# CM5_GPIO.net
KiCad netlist of a schematic drawn in Altium Designer
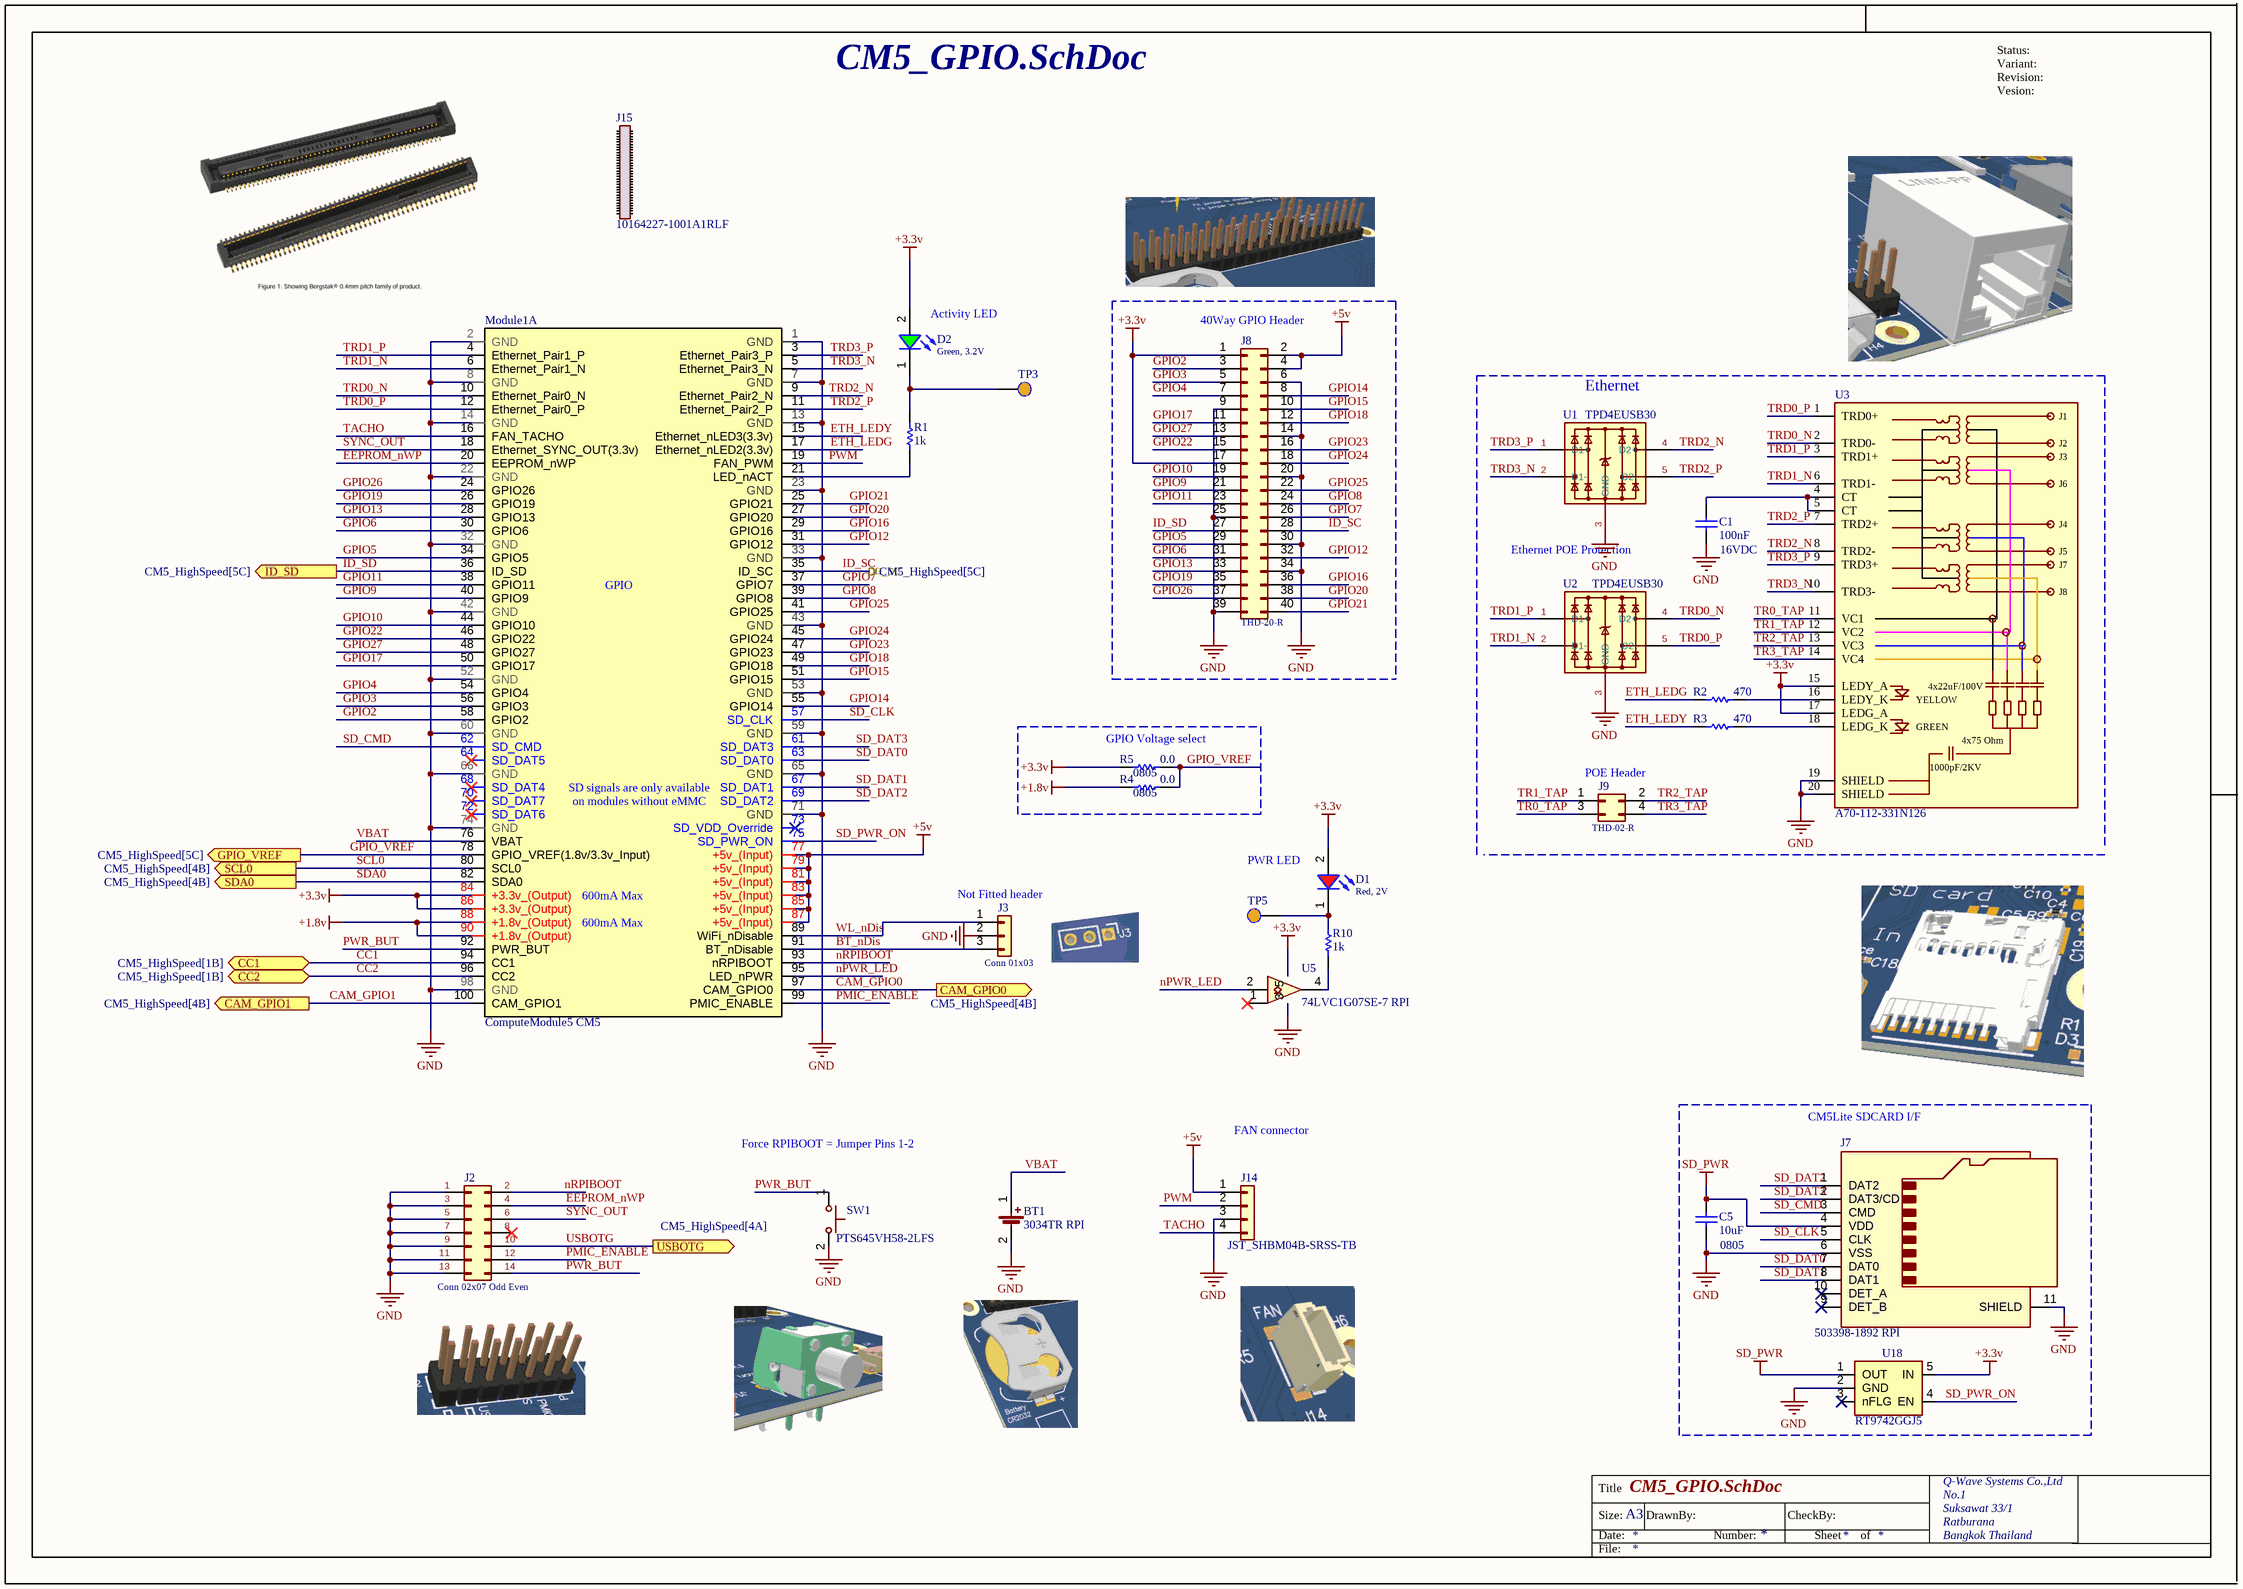
[diagram p0: CM5_GPIO.SchDoc]

(export (version "E")
  (design (tool "Eeschema 10.0.6"))
  (components
    (comp (ref "BT1")
      (value "3034TR RPI")
      (footprint "3034TR RPI")
      (description "Coin Cell Battery Holders COIN CELL RETAINER T APE/REEL 500PC")
      (libsource (lib "Q-WAVE SYSTEMS CO") (part "3034TR RPI"))
    )
    (comp (ref "C1")
      (value "100nF")
      (footprint "WCAP-CSGP_0402_H=0.5mm")
      (description "WCAP-CSGP Multilayer Ceramic Chip Capacitor, General Purpose, size 0402, X5R, 100nF, 16V")
      (fields
        (field (name "MANUFACTURER PART NUMBER") "885012105016")
        (field (name "MANUFACTURER") "Wurth Elektronik")
        (field (name "RATED VOLTAGE") "16VDC")
      )
      (libsource (lib "") (part "Symbol_2"))
    )
    (comp (ref "C5")
      (value "10uF")
      (footprint "WCAP-CSGP_0805_H=1.25mm")
      (description "WCAP-CSGP Multilayer Ceramic Chip Capacitor, General Purpose, size 0805, X5R, 10uF, 16V")
      (fields
        (field (name "MANUFACTURER") "Wurth Elektronik")
        (field (name "MANUFACTURER PART NUMBER") "885012107014")
        (field (name "SIZE") "0805")
      )
      (libsource (lib "") (part "Symbol_2"))
    )
    (comp (ref "D1")
      (value "Red, 2V")
      (footprint "WL-SMCW_0603_H=0.7mm_Red")
      (description "WL-SMCW SMT Mono-color Chip LED Waterclear, size 0603, Red, 2V, 140deg")
      (fields (field (name "PART NUMBER") "150060RS75000") (field (name "PUBLISHER") "Wurth Elektronik"))
      (libsource (lib "Q-WAVE SYSTEMS CO") (part "Symbol"))
    )
    (comp (ref "D2")
      (value "Green, 3.2V")
      (footprint "WL-SMCW_0603_H=0.7mm_Green")
      (description "WL-SMCW SMT Mono-color Chip LED Waterclear, size 0603, Green, 3.2V, 140deg")
      (fields (field (name "PART NUMBER") "150060GS75000") (field (name "PUBLISHER") "Wurth Elektronik"))
      (libsource (lib "Q-WAVE SYSTEMS CO") (part "Symbol"))
    )
    (comp (ref "J2")
      (value "Conn 02x07 Odd Even")
      (footprint "Conn 02x07 Odd Even")
      (description "PinHeader 2x07 P2.54mm Vertical")
      (fields
        (field (name "MANUFACTURER") "Wurth Elektronik")
        (field (name "MANUFACTURER PART NUMBER") "61301421121")
      )
      (libsource (lib "Q-WAVE SYSTEMS CO") (part "Conn 02x07 Odd Even"))
    )
    (comp (ref "J3")
      (value "Conn 01x03")
      (footprint "Conn 01x03")
      (description "PinHeader_1x03_P2.54mm_Vertical")
      (fields
        (field (name "MANUFACTURER") "Wurth Elektronik")
        (field (name "MANUFACTURER PART NUMBER") "61300311121")
      )
      (libsource (lib "Q-WAVE SYSTEMS CO") (part "Conn 01x03"))
    )
    (comp (ref "J7")
      (value "503398-1892 RPI")
      (footprint "503398-1892 RPI")
      (libsource (lib "Q-WAVE SYSTEMS CO") (part "503398-1892 RPI"))
    )
    (comp (ref "J8")
      (value "THD-20-R")
      (footprint "THD-20-R")
      (description "Through hole straight pin header, 2x20, 2.54mm pitch, double rows")
      (fields
        (field (name "MANUFACTURER PART NUMBER") "61304021121")
        (field (name "MANUFACTURER") "Wurth Elektronik")
      )
      (libsource (lib "Q-WAVE SYSTEMS CO") (part "THD-20-R"))
    )
    (comp (ref "J9")
      (value "THD-02-R")
      (footprint "THD-02-R")
      (description "PinHeader 2x02 P2.54mm Vertical")
      (fields
        (field (name "MANUFACTURER") "Wurth Elektronik")
        (field (name "MANUFACTURER PART NUMBER") "61300421121")
      )
      (libsource (lib "Q-WAVE SYSTEMS CO") (part "THD-02-R"))
    )
    (comp (ref "J14")
      (value "JST_SHBM04B-SRSS-TB")
      (footprint "JST_SHBM04B-SRSS-TB")
      (description "Board Connector, 4 Contact(s), 1 Row(s), Male, Straight, Surface Mount Terminal")
      (libsource (lib "Q-WAVE SYSTEMS CO") (part "JST_SHBM04B-SRSS-TB"))
    )
    (comp (ref "J15")
      (value "10164227-1001A1RLF")
      (footprint "CM5-BergStak-10164227")
      (description "CM5 1.5mm Height 0.4MM Btb, 100P, Receptacle, 1.5MM Stack Height")
      (libsource (lib "Q-WAVE SYSTEMS CO") (part "10164227-1001A1RLF"))
    )
    (comp (ref "Module1")
      (value "ComputeModule5 CM5")
      (footprint "ComputeModule5-CM5")
      (description "Raspberry Pi Compute Module 5")
      (libsource (lib "Q-WAVE SYSTEMS CO") (part "ComputeModule5-CM5"))
    )
    (comp (ref "R1")
      (value "1k")
      (footprint "SMD-0402-RES")
      (description "RES SMD 1K OHM 1% 1/10W 0402")
      (fields
        (field (name "MANUFACTURER") "Panasonic Electronic Components")
        (field (name "TOLERANCE") "±1%")
      )
      (libsource (lib "Q-WAVE SYSTEMS CO") (part "resistor"))
    )
    (comp (ref "R2")
      (value "470")
      (footprint "SMD-0402-RES")
      (description "RES SMD 470 OHM 1% 1/10W 0402")
      (fields (field (name "PART NUMBER") "ERJ-2RKF4700X") (field (name "DIGI-KEY PART NUMBER") "P470LCT-ND"))
      (libsource (lib "Q-WAVE SYSTEMS CO") (part "resistor"))
    )
    (comp (ref "R3")
      (value "470")
      (footprint "SMD-0402-RES")
      (description "RES SMD 470 OHM 1% 1/10W 0402")
      (fields (field (name "PART NUMBER") "ERJ-2RKF4700X") (field (name "DIGI-KEY PART NUMBER") "P470LCT-ND"))
      (libsource (lib "Q-WAVE SYSTEMS CO") (part "resistor"))
    )
    (comp (ref "R4")
      (value "0.0")
      (footprint "SMD-0805-RES")
      (description "RES SMD 0.0 OHM JUMPER 1/8W 0805")
      (fields
        (field (name "TOLERANCE") "Jumper")
        (field (name "PART NUMBER") "ERJ-6GEY0R00V")
        (field (name "SUPPLIER DEVICE PACKAGE") "0805")
      )
      (libsource (lib "") (part "Symbol_1"))
    )
    (comp (ref "R5")
      (value "0.0")
      (footprint "SMD-0805-RES")
      (description "RES SMD 0.0 OHM JUMPER 1/8W 0805")
      (fields
        (field (name "TOLERANCE") "Jumper")
        (field (name "PART NUMBER") "ERJ-6GEY0R00V")
        (field (name "SUPPLIER DEVICE PACKAGE") "0805")
      )
      (libsource (lib "") (part "Symbol_1"))
    )
    (comp (ref "R10")
      (value "1k")
      (footprint "SMD-0402-RES")
      (description "RES SMD 1K OHM 1% 1/10W 0402")
      (fields
        (field (name "MANUFACTURER") "Panasonic Electronic Components")
        (field (name "TOLERANCE") "±1%")
      )
      (libsource (lib "Q-WAVE SYSTEMS CO") (part "resistor"))
    )
    (comp (ref "SW1")
      (value "PTS645VH58-2LFS")
      (footprint "PTS645VH58-2LFS")
      (description "PTS645 Series Compact 6 x 6 mm SPST 2 N Through Hole Tactile Switch")
      (libsource (lib "Q-WAVE SYSTEMS CO") (part "PTS645VH58-2LFS"))
    )
    (comp (ref "TP3")
      (value "TEST_POINT 1")
      (footprint "TEST_POINT 1")
      (description "Test Point SMT PAD")
      (libsource (lib "Q-WAVE SYSTEMS CO") (part "TEST_POINT 1"))
    )
    (comp (ref "TP5")
      (value "TEST_POINT 1")
      (footprint "TEST_POINT 1")
      (description "Test Point SMT PAD")
      (libsource (lib "Q-WAVE SYSTEMS CO") (part "TEST_POINT 1"))
    )
    (comp (ref "U1")
      (value "TPD4EUSB30")
      (footprint "TPD4EUSB30")
      (libsource (lib "Q-WAVE SYSTEMS CO") (part "TPD4EUSB30"))
    )
    (comp (ref "U2")
      (value "TPD4EUSB30")
      (footprint "TPD4EUSB30")
      (libsource (lib "Q-WAVE SYSTEMS CO") (part "TPD4EUSB30"))
    )
    (comp (ref "U3")
      (value "A70-112-331N126")
      (footprint "A70-112-331N126")
      (libsource (lib "Q-WAVE SYSTEMS CO") (part "A70-112-331N126"))
    )
    (comp (ref "U5")
      (value "74LVC1G07SE-7 RPI")
      (footprint "74LVC1G07SE-7 RPI")
      (description "74LVC Series 5.5 V Surface Mount Single Buffer with Open Drain Output - SOT-353")
      (libsource (lib "Q-WAVE SYSTEMS CO") (part "74LVC1G07SE-7 RPI"))
    )
    (comp (ref "U18")
      (value "RT9742GGJ5")
      (footprint "FP-RT9742GGJ5-IPC_A")
      (description "IC Pwr Swtch N-chan 1: 1 TSOT23-5")
      (libsource (lib "Q-WAVE SYSTEMS CO") (part "RT9742GGJ5"))
    )
  )
  (nets
    (net (code "1") (name "+1.8v") (class "Default")
      (node (ref "Module1") (pin "88") (pinfunction "+1.8v_(Output)_88") (pintype "passive"))
      (node (ref "Module1") (pin "90") (pinfunction "+1.8v_(Output)_90") (pintype "passive"))
      (node (ref "R4") (pin "1") (pinfunction "1_1") (pintype "passive"))
    )
    (net (code "2") (name "+3.3v") (class "Default")
      (node (ref "D1") (pin "2") (pinfunction "A_2") (pintype "passive"))
      (node (ref "D2") (pin "2") (pinfunction "A_2") (pintype "passive"))
      (node (ref "J8") (pin "1") (pinfunction "Pin_1_1") (pintype "passive"))
      (node (ref "J8") (pin "17") (pinfunction "Pin_17_17") (pintype "passive"))
      (node (ref "Module1") (pin "84") (pinfunction "+3.3v_(Output)_84") (pintype "passive"))
      (node (ref "Module1") (pin "86") (pinfunction "+3.3v_(Output)_86") (pintype "passive"))
      (node (ref "R5") (pin "1") (pinfunction "1_1") (pintype "passive"))
      (node (ref "U18") (pin "5") (pinfunction "IN_5") (pintype "passive"))
      (node (ref "U3") (pin "15") (pinfunction "LEDY_A_15") (pintype "passive"))
      (node (ref "U3") (pin "17") (pinfunction "LEDG_A_17") (pintype "passive"))
      (node (ref "U5") (pin "5") (pinfunction "VCC_5") (pintype "passive"))
    )
    (net (code "3") (name "+5v") (class "Default")
      (node (ref "J14") (pin "1") (pinfunction "Pin_1_1") (pintype "passive"))
      (node (ref "J8") (pin "2") (pinfunction "Pin_2_2") (pintype "passive"))
      (node (ref "J8") (pin "4") (pinfunction "Pin_4_4") (pintype "passive"))
      (node (ref "Module1") (pin "77") (pinfunction "+5v_(Input)_77") (pintype "passive"))
      (node (ref "Module1") (pin "79") (pinfunction "+5v_(Input)_79") (pintype "passive"))
      (node (ref "Module1") (pin "81") (pinfunction "+5v_(Input)_81") (pintype "passive"))
      (node (ref "Module1") (pin "83") (pinfunction "+5v_(Input)_83") (pintype "passive"))
      (node (ref "Module1") (pin "85") (pinfunction "+5v_(Input)_85") (pintype "passive"))
      (node (ref "Module1") (pin "87") (pinfunction "+5v_(Input)_87") (pintype "passive"))
    )
    (net (code "4") (name "/BT_nDis") (class "Default")
      (node (ref "J3") (pin "3") (pinfunction "Pin_3_3") (pintype "passive"))
      (node (ref "Module1") (pin "91") (pinfunction "BT_nDisable_91") (pintype "passive"))
    )
    (net (code "5") (name "/CAM_GPIO0") (class "Default")
      (node (ref "Module1") (pin "97") (pinfunction "CAM_GPIO0_97") (pintype "passive"))
    )
    (net (code "6") (name "/CAM_GPIO1") (class "Default")
      (node (ref "Module1") (pin "100") (pinfunction "CAM_GPIO1_100") (pintype "passive"))
    )
    (net (code "7") (name "/CC1") (class "Default")
      (node (ref "Module1") (pin "94") (pinfunction "CC1_94") (pintype "passive"))
    )
    (net (code "8") (name "/CC2") (class "Default")
      (node (ref "Module1") (pin "96") (pinfunction "CC2_96") (pintype "passive"))
    )
    (net (code "9") (name "/EEPROM_nWP") (class "Default")
      (node (ref "J2") (pin "4") (pinfunction "Pin_4_4") (pintype "passive"))
      (node (ref "Module1") (pin "20") (pinfunction "EEPROM_nWP_20") (pintype "passive"))
    )
    (net (code "10") (name "/ETH_LEDG") (class "Default")
      (node (ref "Module1") (pin "17") (pinfunction "Ethernet_nLED2(3.3v)_17") (pintype "passive"))
      (node (ref "R2") (pin "1") (pinfunction "1_1") (pintype "passive"))
    )
    (net (code "11") (name "/ETH_LEDY") (class "Default")
      (node (ref "Module1") (pin "15") (pinfunction "Ethernet_nLED3(3.3v)_15") (pintype "passive"))
      (node (ref "R3") (pin "1") (pinfunction "1_1") (pintype "passive"))
    )
    (net (code "12") (name "/GPIO2") (class "Default")
      (node (ref "J8") (pin "3") (pinfunction "Pin_3_3") (pintype "passive"))
      (node (ref "Module1") (pin "58") (pinfunction "GPIO2_58") (pintype "passive"))
    )
    (net (code "13") (name "/GPIO3") (class "Default")
      (node (ref "J8") (pin "5") (pinfunction "Pin_5_5") (pintype "passive"))
      (node (ref "Module1") (pin "56") (pinfunction "GPIO3_56") (pintype "passive"))
    )
    (net (code "14") (name "/GPIO4") (class "Default")
      (node (ref "J8") (pin "7") (pinfunction "Pin_7_7") (pintype "passive"))
      (node (ref "Module1") (pin "54") (pinfunction "GPIO4_54") (pintype "passive"))
    )
    (net (code "15") (name "/GPIO5") (class "Default")
      (node (ref "J8") (pin "29") (pinfunction "Pin_29_29") (pintype "passive"))
      (node (ref "Module1") (pin "34") (pinfunction "GPIO5_34") (pintype "passive"))
    )
    (net (code "16") (name "/GPIO6") (class "Default")
      (node (ref "J8") (pin "31") (pinfunction "Pin_31_31") (pintype "passive"))
      (node (ref "Module1") (pin "30") (pinfunction "GPIO6_30") (pintype "passive"))
    )
    (net (code "17") (name "/GPIO7") (class "Default")
      (node (ref "J8") (pin "26") (pinfunction "Pin_26_26") (pintype "passive"))
      (node (ref "Module1") (pin "37") (pinfunction "GPIO7_37") (pintype "passive"))
    )
    (net (code "18") (name "/GPIO8") (class "Default")
      (node (ref "J8") (pin "24") (pinfunction "Pin_24_24") (pintype "passive"))
      (node (ref "Module1") (pin "39") (pinfunction "GPIO8_39") (pintype "passive"))
    )
    (net (code "19") (name "/GPIO9") (class "Default")
      (node (ref "J8") (pin "21") (pinfunction "Pin_21_21") (pintype "passive"))
      (node (ref "Module1") (pin "40") (pinfunction "GPIO9_40") (pintype "passive"))
    )
    (net (code "20") (name "/GPIO10") (class "Default")
      (node (ref "J8") (pin "19") (pinfunction "Pin_19_19") (pintype "passive"))
      (node (ref "Module1") (pin "44") (pinfunction "GPIO10_44") (pintype "passive"))
    )
    (net (code "21") (name "/GPIO11") (class "Default")
      (node (ref "J8") (pin "23") (pinfunction "Pin_23_23") (pintype "passive"))
      (node (ref "Module1") (pin "38") (pinfunction "GPIO11_38") (pintype "passive"))
    )
    (net (code "22") (name "/GPIO12") (class "Default")
      (node (ref "J8") (pin "32") (pinfunction "Pin_32_32") (pintype "passive"))
      (node (ref "Module1") (pin "31") (pinfunction "GPIO12_31") (pintype "passive"))
    )
    (net (code "23") (name "/GPIO13") (class "Default")
      (node (ref "J8") (pin "33") (pinfunction "Pin_33_33") (pintype "passive"))
      (node (ref "Module1") (pin "28") (pinfunction "GPIO13_28") (pintype "passive"))
    )
    (net (code "24") (name "/GPIO14") (class "Default")
      (node (ref "J8") (pin "8") (pinfunction "Pin_8_8") (pintype "passive"))
      (node (ref "Module1") (pin "55") (pinfunction "GPIO14_55") (pintype "passive"))
    )
    (net (code "25") (name "/GPIO15") (class "Default")
      (node (ref "J8") (pin "10") (pinfunction "Pin_10_10") (pintype "passive"))
      (node (ref "Module1") (pin "51") (pinfunction "GPIO15_51") (pintype "passive"))
    )
    (net (code "26") (name "/GPIO16") (class "Default")
      (node (ref "J8") (pin "36") (pinfunction "Pin_36_36") (pintype "passive"))
      (node (ref "Module1") (pin "29") (pinfunction "GPIO16_29") (pintype "passive"))
    )
    (net (code "27") (name "/GPIO17") (class "Default")
      (node (ref "J8") (pin "11") (pinfunction "Pin_11_11") (pintype "passive"))
      (node (ref "Module1") (pin "50") (pinfunction "GPIO17_50") (pintype "passive"))
    )
    (net (code "28") (name "/GPIO18") (class "Default")
      (node (ref "J8") (pin "12") (pinfunction "Pin_12_12") (pintype "passive"))
      (node (ref "Module1") (pin "49") (pinfunction "GPIO18_49") (pintype "passive"))
    )
    (net (code "29") (name "/GPIO19") (class "Default")
      (node (ref "J8") (pin "35") (pinfunction "Pin_35_35") (pintype "passive"))
      (node (ref "Module1") (pin "26") (pinfunction "GPIO19_26") (pintype "passive"))
    )
    (net (code "30") (name "/GPIO20") (class "Default")
      (node (ref "J8") (pin "38") (pinfunction "Pin_38_38") (pintype "passive"))
      (node (ref "Module1") (pin "27") (pinfunction "GPIO20_27") (pintype "passive"))
    )
    (net (code "31") (name "/GPIO21") (class "Default")
      (node (ref "J8") (pin "40") (pinfunction "Pin_40_40") (pintype "passive"))
      (node (ref "Module1") (pin "25") (pinfunction "GPIO21_25") (pintype "passive"))
    )
    (net (code "32") (name "/GPIO22") (class "Default")
      (node (ref "J8") (pin "15") (pinfunction "Pin_15_15") (pintype "passive"))
      (node (ref "Module1") (pin "46") (pinfunction "GPIO22_46") (pintype "passive"))
    )
    (net (code "33") (name "/GPIO23") (class "Default")
      (node (ref "J8") (pin "16") (pinfunction "Pin_16_16") (pintype "passive"))
      (node (ref "Module1") (pin "47") (pinfunction "GPIO23_47") (pintype "passive"))
    )
    (net (code "34") (name "/GPIO24") (class "Default")
      (node (ref "J8") (pin "18") (pinfunction "Pin_18_18") (pintype "passive"))
      (node (ref "Module1") (pin "45") (pinfunction "GPIO24_45") (pintype "passive"))
    )
    (net (code "35") (name "/GPIO25") (class "Default")
      (node (ref "J8") (pin "22") (pinfunction "Pin_22_22") (pintype "passive"))
      (node (ref "Module1") (pin "41") (pinfunction "GPIO25_41") (pintype "passive"))
    )
    (net (code "36") (name "/GPIO26") (class "Default")
      (node (ref "J8") (pin "37") (pinfunction "Pin_37_37") (pintype "passive"))
      (node (ref "Module1") (pin "24") (pinfunction "GPIO26_24") (pintype "passive"))
    )
    (net (code "37") (name "/GPIO27") (class "Default")
      (node (ref "J8") (pin "13") (pinfunction "Pin_13_13") (pintype "passive"))
      (node (ref "Module1") (pin "48") (pinfunction "GPIO27_48") (pintype "passive"))
    )
    (net (code "38") (name "/GPIO_VREF") (class "Default")
      (node (ref "Module1") (pin "78") (pinfunction "GPIO_VREF(1.8v/3.3v_Input)_78") (pintype "passive"))
      (node (ref "R4") (pin "2") (pinfunction "2_2") (pintype "passive"))
      (node (ref "R5") (pin "2") (pinfunction "2_2") (pintype "passive"))
    )
    (net (code "39") (name "/ID_SC") (class "Default")
      (node (ref "J8") (pin "28") (pinfunction "Pin_28_28") (pintype "passive"))
      (node (ref "Module1") (pin "35") (pinfunction "ID_SC_35") (pintype "passive"))
    )
    (net (code "40") (name "/ID_SD") (class "Default")
      (node (ref "J8") (pin "27") (pinfunction "Pin_27_27") (pintype "passive"))
      (node (ref "Module1") (pin "36") (pinfunction "ID_SD_36") (pintype "passive"))
    )
    (net (code "41") (name "/PMIC_ENABLE") (class "Default")
      (node (ref "J2") (pin "12") (pinfunction "Pin_12_12") (pintype "passive"))
      (node (ref "Module1") (pin "99") (pinfunction "PMIC_ENABLE_99") (pintype "passive"))
    )
    (net (code "42") (name "/PWM") (class "Default")
      (node (ref "J14") (pin "2") (pinfunction "Pin_2_2") (pintype "passive"))
      (node (ref "Module1") (pin "19") (pinfunction "FAN_PWM_19") (pintype "passive"))
    )
    (net (code "43") (name "/PWR_BUT") (class "Default")
      (node (ref "J2") (pin "14") (pinfunction "Pin_14_14") (pintype "passive"))
      (node (ref "Module1") (pin "92") (pinfunction "PWR_BUT_92") (pintype "passive"))
      (node (ref "SW1") (pin "1") (pinfunction "1_1") (pintype "passive"))
    )
    (net (code "44") (name "/SCL0") (class "Default")
      (node (ref "Module1") (pin "80") (pinfunction "SCL0_80") (pintype "passive"))
    )
    (net (code "45") (name "/SDA0") (class "Default")
      (node (ref "Module1") (pin "82") (pinfunction "SDA0_82") (pintype "passive"))
    )
    (net (code "46") (name "/SD_CLK") (class "Default")
      (node (ref "J7") (pin "5") (pinfunction "CLK_5") (pintype "passive"))
      (node (ref "Module1") (pin "57") (pinfunction "SD_CLK_57") (pintype "passive"))
    )
    (net (code "47") (name "/SD_CMD") (class "Default")
      (node (ref "J7") (pin "3") (pinfunction "CMD_3") (pintype "passive"))
      (node (ref "Module1") (pin "62") (pinfunction "SD_CMD_62") (pintype "passive"))
    )
    (net (code "48") (name "/SD_DAT0") (class "Default")
      (node (ref "J7") (pin "7") (pinfunction "DAT0_7") (pintype "passive"))
      (node (ref "Module1") (pin "63") (pinfunction "SD_DAT0_63") (pintype "passive"))
    )
    (net (code "49") (name "/SD_DAT1") (class "Default")
      (node (ref "J7") (pin "8") (pinfunction "DAT1_8") (pintype "passive"))
      (node (ref "Module1") (pin "67") (pinfunction "SD_DAT1_67") (pintype "passive"))
    )
    (net (code "50") (name "/SD_DAT2") (class "Default")
      (node (ref "J7") (pin "1") (pinfunction "DAT2_1") (pintype "passive"))
      (node (ref "Module1") (pin "69") (pinfunction "SD_DAT2_69") (pintype "passive"))
    )
    (net (code "51") (name "/SD_DAT3") (class "Default")
      (node (ref "J7") (pin "2") (pinfunction "DAT3/CD_2") (pintype "passive"))
      (node (ref "Module1") (pin "61") (pinfunction "SD_DAT3_61") (pintype "passive"))
    )
    (net (code "52") (name "/SD_PWR_ON") (class "Default")
      (node (ref "Module1") (pin "75") (pinfunction "SD_PWR_ON_75") (pintype "passive"))
      (node (ref "U18") (pin "4") (pinfunction "EN_4") (pintype "passive"))
    )
    (net (code "53") (name "/SYNC_OUT") (class "Default")
      (node (ref "J2") (pin "6") (pinfunction "Pin_6_6") (pintype "passive"))
      (node (ref "Module1") (pin "18") (pinfunction "Ethernet_SYNC_OUT(3.3v)_18") (pintype "passive"))
    )
    (net (code "54") (name "/TACHO") (class "Default")
      (node (ref "J14") (pin "4") (pinfunction "Pin_4_4") (pintype "passive"))
      (node (ref "Module1") (pin "16") (pinfunction "FAN_TACHO_16") (pintype "passive"))
    )
    (net (code "55") (name "/TR0_TAP") (class "Default")
      (node (ref "J9") (pin "3") (pinfunction "Pin_3_3") (pintype "passive"))
      (node (ref "U3") (pin "11") (pinfunction "VC1_11") (pintype "passive"))
    )
    (net (code "56") (name "/TR1_TAP") (class "Default")
      (node (ref "J9") (pin "1") (pinfunction "Pin_1_1") (pintype "passive"))
      (node (ref "U3") (pin "12") (pinfunction "VC2_12") (pintype "passive"))
    )
    (net (code "57") (name "/TR2_TAP") (class "Default")
      (node (ref "J9") (pin "2") (pinfunction "Pin_2_2") (pintype "passive"))
      (node (ref "U3") (pin "13") (pinfunction "VC3_13") (pintype "passive"))
    )
    (net (code "58") (name "/TR3_TAP") (class "Default")
      (node (ref "J9") (pin "4") (pinfunction "Pin_4_4") (pintype "passive"))
      (node (ref "U3") (pin "14") (pinfunction "VC4_14") (pintype "passive"))
    )
    (net (code "59") (name "/TRD0_N") (class "Default")
      (node (ref "Module1") (pin "10") (pinfunction "Ethernet_Pair0_N_10") (pintype "passive"))
      (node (ref "U2") (pin "4") (pinfunction "D2+_4") (pintype "passive"))
      (node (ref "U3") (pin "2") (pinfunction "TRD0-_2") (pintype "passive"))
    )
    (net (code "60") (name "/TRD0_P") (class "Default")
      (node (ref "Module1") (pin "12") (pinfunction "Ethernet_Pair0_P_12") (pintype "passive"))
      (node (ref "U2") (pin "5") (pinfunction "D2-_5") (pintype "passive"))
      (node (ref "U3") (pin "1") (pinfunction "TRD0+_1") (pintype "passive"))
    )
    (net (code "61") (name "/TRD1_N") (class "Default")
      (node (ref "Module1") (pin "6") (pinfunction "Ethernet_Pair1_N_6") (pintype "passive"))
      (node (ref "U2") (pin "2") (pinfunction "D1-_2") (pintype "passive"))
      (node (ref "U3") (pin "6") (pinfunction "TRD1-_6") (pintype "passive"))
    )
    (net (code "62") (name "/TRD1_P") (class "Default")
      (node (ref "Module1") (pin "4") (pinfunction "Ethernet_Pair1_P_4") (pintype "passive"))
      (node (ref "U2") (pin "1") (pinfunction "D1+_1") (pintype "passive"))
      (node (ref "U3") (pin "3") (pinfunction "TRD1+_3") (pintype "passive"))
    )
    (net (code "63") (name "/TRD2_N") (class "Default")
      (node (ref "Module1") (pin "9") (pinfunction "Ethernet_Pair2_N_9") (pintype "passive"))
      (node (ref "U1") (pin "4") (pinfunction "D2+_4") (pintype "passive"))
      (node (ref "U3") (pin "8") (pinfunction "TRD2-_8") (pintype "passive"))
    )
    (net (code "64") (name "/TRD2_P") (class "Default")
      (node (ref "Module1") (pin "11") (pinfunction "Ethernet_Pair2_P_11") (pintype "passive"))
      (node (ref "U1") (pin "5") (pinfunction "D2-_5") (pintype "passive"))
      (node (ref "U3") (pin "7") (pinfunction "TRD2+_7") (pintype "passive"))
    )
    (net (code "65") (name "/TRD3_N") (class "Default")
      (node (ref "Module1") (pin "5") (pinfunction "Ethernet_Pair3_N_5") (pintype "passive"))
      (node (ref "U1") (pin "2") (pinfunction "D1-_2") (pintype "passive"))
      (node (ref "U3") (pin "10") (pinfunction "TRD3-_10") (pintype "passive"))
    )
    (net (code "66") (name "/TRD3_P") (class "Default")
      (node (ref "Module1") (pin "3") (pinfunction "Ethernet_Pair3_P_3") (pintype "passive"))
      (node (ref "U1") (pin "1") (pinfunction "D1+_1") (pintype "passive"))
      (node (ref "U3") (pin "9") (pinfunction "TRD3+_9") (pintype "passive"))
    )
    (net (code "67") (name "/USBOTG") (class "Default")
      (node (ref "J2") (pin "10") (pinfunction "Pin_10_10") (pintype "passive"))
    )
    (net (code "68") (name "/VBAT") (class "Default")
      (node (ref "BT1") (pin "1") (pinfunction "+_1") (pintype "passive"))
      (node (ref "Module1") (pin "76") (pinfunction "VBAT_76") (pintype "passive"))
    )
    (net (code "69") (name "/WL_nDis") (class "Default")
      (node (ref "J3") (pin "1") (pinfunction "Pin_1_1") (pintype "passive"))
      (node (ref "Module1") (pin "89") (pinfunction "WiFi_nDisable_89") (pintype "passive"))
    )
    (net (code "70") (name "/nPWR_LED") (class "Default")
      (node (ref "Module1") (pin "95") (pinfunction "LED_nPWR_95") (pintype "passive"))
      (node (ref "U5") (pin "2") (pinfunction "2_2") (pintype "passive"))
    )
    (net (code "71") (name "/nRPIBOOT") (class "Default")
      (node (ref "J2") (pin "2") (pinfunction "Pin_2_2") (pintype "passive"))
      (node (ref "Module1") (pin "93") (pinfunction "nRPIBOOT_93") (pintype "passive"))
    )
    (net (code "72") (name "GND") (class "Default")
      (node (ref "BT1") (pin "2") (pinfunction "-_2") (pintype "passive"))
      (node (ref "C1") (pin "1") (pinfunction "1_1") (pintype "passive"))
      (node (ref "C5") (pin "1") (pinfunction "1_1") (pintype "passive"))
      (node (ref "J14") (pin "3") (pinfunction "Pin_3_3") (pintype "passive"))
      (node (ref "J2") (pin "1") (pinfunction "Pin_1_1") (pintype "passive"))
      (node (ref "J2") (pin "11") (pinfunction "Pin_11_11") (pintype "passive"))
      (node (ref "J2") (pin "13") (pinfunction "Pin_13_13") (pintype "passive"))
      (node (ref "J2") (pin "3") (pinfunction "Pin_3_3") (pintype "passive"))
      (node (ref "J2") (pin "5") (pinfunction "Pin_5_5") (pintype "passive"))
      (node (ref "J2") (pin "7") (pinfunction "Pin_7_7") (pintype "passive"))
      (node (ref "J2") (pin "9") (pinfunction "Pin_9_9") (pintype "passive"))
      (node (ref "J3") (pin "2") (pinfunction "Pin_2_2") (pintype "passive"))
      (node (ref "J7") (pin "11") (pinfunction "SHIELD_11") (pintype "passive"))
      (node (ref "J7") (pin "6") (pinfunction "VSS_6") (pintype "passive"))
      (node (ref "J8") (pin "14") (pinfunction "Pin_14_14") (pintype "passive"))
      (node (ref "J8") (pin "20") (pinfunction "Pin_20_20") (pintype "passive"))
      (node (ref "J8") (pin "25") (pinfunction "Pin_25_25") (pintype "passive"))
      (node (ref "J8") (pin "30") (pinfunction "Pin_30_30") (pintype "passive"))
      (node (ref "J8") (pin "34") (pinfunction "Pin_34_34") (pintype "passive"))
      (node (ref "J8") (pin "39") (pinfunction "Pin_39_39") (pintype "passive"))
      (node (ref "J8") (pin "6") (pinfunction "Pin_6_6") (pintype "passive"))
      (node (ref "J8") (pin "9") (pinfunction "Pin_9_9") (pintype "passive"))
      (node (ref "Module1") (pin "1") (pinfunction "GND_1") (pintype "passive"))
      (node (ref "Module1") (pin "13") (pinfunction "GND_13") (pintype "passive"))
      (node (ref "Module1") (pin "14") (pinfunction "GND_14") (pintype "passive"))
      (node (ref "Module1") (pin "2") (pinfunction "GND_2") (pintype "passive"))
      (node (ref "Module1") (pin "22") (pinfunction "GND_22") (pintype "passive"))
      (node (ref "Module1") (pin "23") (pinfunction "GND_23") (pintype "passive"))
      (node (ref "Module1") (pin "32") (pinfunction "GND_32") (pintype "passive"))
      (node (ref "Module1") (pin "33") (pinfunction "GND_33") (pintype "passive"))
      (node (ref "Module1") (pin "42") (pinfunction "GND_42") (pintype "passive"))
      (node (ref "Module1") (pin "43") (pinfunction "GND_43") (pintype "passive"))
      (node (ref "Module1") (pin "52") (pinfunction "GND_52") (pintype "passive"))
      (node (ref "Module1") (pin "53") (pinfunction "GND_53") (pintype "passive"))
      (node (ref "Module1") (pin "59") (pinfunction "GND_59") (pintype "passive"))
      (node (ref "Module1") (pin "60") (pinfunction "GND_60") (pintype "passive"))
      (node (ref "Module1") (pin "65") (pinfunction "GND_65") (pintype "passive"))
      (node (ref "Module1") (pin "66") (pinfunction "GND_66") (pintype "passive"))
      (node (ref "Module1") (pin "7") (pinfunction "GND_7") (pintype "passive"))
      (node (ref "Module1") (pin "71") (pinfunction "GND_71") (pintype "passive"))
      (node (ref "Module1") (pin "74") (pinfunction "GND_74") (pintype "passive"))
      (node (ref "Module1") (pin "8") (pinfunction "GND_8") (pintype "passive"))
      (node (ref "Module1") (pin "98") (pinfunction "GND_98") (pintype "passive"))
      (node (ref "SW1") (pin "2") (pinfunction "2_2") (pintype "passive"))
      (node (ref "U1") (pin "3") (pinfunction "GND_3") (pintype "passive"))
      (node (ref "U18") (pin "2") (pinfunction "GND_2") (pintype "passive"))
      (node (ref "U2") (pin "3") (pinfunction "GND_3") (pintype "passive"))
      (node (ref "U3") (pin "19") (pinfunction "SHIELD_19") (pintype "passive"))
      (node (ref "U3") (pin "20") (pinfunction "SHIELD_20") (pintype "passive"))
      (node (ref "U5") (pin "3") (pinfunction "GND_3") (pintype "passive"))
    )
    (net (code "73") (name "Net-(C1-Pad2)") (class "Default")
      (node (ref "C1") (pin "2") (pinfunction "2_2") (pintype "passive"))
      (node (ref "U3") (pin "4") (pinfunction "CT_4") (pintype "passive"))
      (node (ref "U3") (pin "5") (pinfunction "CT_5") (pintype "passive"))
    )
    (net (code "74") (name "Net-(D1-K)") (class "Default")
      (node (ref "D1") (pin "1") (pinfunction "K_1") (pintype "passive"))
      (node (ref "R10") (pin "2") (pinfunction "2_2") (pintype "passive"))
      (node (ref "TP5") (pin "1") (pinfunction "1_1") (pintype "passive"))
    )
    (net (code "75") (name "Net-(D2-K)") (class "Default")
      (node (ref "D2") (pin "1") (pinfunction "K_1") (pintype "passive"))
      (node (ref "R1") (pin "2") (pinfunction "2_2") (pintype "passive"))
      (node (ref "TP3") (pin "1") (pinfunction "1_1") (pintype "passive"))
    )
    (net (code "76") (name "Net-(Module1A-LED_nACT)") (class "Default")
      (node (ref "Module1") (pin "21") (pinfunction "LED_nACT_21") (pintype "passive"))
      (node (ref "R1") (pin "1") (pinfunction "1_1") (pintype "passive"))
    )
    (net (code "77") (name "Net-(R10-Pad1)") (class "Default")
      (node (ref "R10") (pin "1") (pinfunction "1_1") (pintype "passive"))
      (node (ref "U5") (pin "4") (pinfunction "4_4") (pintype "passive"))
    )
    (net (code "78") (name "Net-(U3-LEDG_K)") (class "Default")
      (node (ref "R3") (pin "2") (pinfunction "2_2") (pintype "passive"))
      (node (ref "U3") (pin "18") (pinfunction "LEDG_K_18") (pintype "passive"))
    )
    (net (code "79") (name "Net-(U3-LEDY_K)") (class "Default")
      (node (ref "R2") (pin "2") (pinfunction "2_2") (pintype "passive"))
      (node (ref "U3") (pin "16") (pinfunction "LEDY_K_16") (pintype "passive"))
    )
    (net (code "80") (name "SD_PWR") (class "Default")
      (node (ref "C5") (pin "2") (pinfunction "2_2") (pintype "passive"))
      (node (ref "J7") (pin "4") (pinfunction "VDD_4") (pintype "passive"))
      (node (ref "U18") (pin "1") (pinfunction "OUT_1") (pintype "passive"))
    )
    (net (code "81") (name "unconnected-(J2-Pin_8-Pad8)") (class "Default")
      (node (ref "J2") (pin "8") (pinfunction "Pin_8_8") (pintype "passive+no_connect"))
    )
    (net (code "82") (name "unconnected-(J7-DET_A-Pad10)") (class "Default")
      (node (ref "J7") (pin "10") (pinfunction "DET_A_10") (pintype "passive+no_connect"))
    )
    (net (code "83") (name "unconnected-(J7-DET_B-Pad9)") (class "Default")
      (node (ref "J7") (pin "9") (pinfunction "DET_B_9") (pintype "passive+no_connect"))
    )
    (net (code "84") (name "unconnected-(Module1A-SD_DAT4-Pad68)") (class "Default")
      (node (ref "Module1") (pin "68") (pinfunction "SD_DAT4_68") (pintype "passive+no_connect"))
    )
    (net (code "85") (name "unconnected-(Module1A-SD_DAT5-Pad64)") (class "Default")
      (node (ref "Module1") (pin "64") (pinfunction "SD_DAT5_64") (pintype "passive+no_connect"))
    )
    (net (code "86") (name "unconnected-(Module1A-SD_DAT6-Pad72)") (class "Default")
      (node (ref "Module1") (pin "72") (pinfunction "SD_DAT6_72") (pintype "passive+no_connect"))
    )
    (net (code "87") (name "unconnected-(Module1A-SD_DAT7-Pad70)") (class "Default")
      (node (ref "Module1") (pin "70") (pinfunction "SD_DAT7_70") (pintype "passive+no_connect"))
    )
    (net (code "88") (name "unconnected-(Module1A-SD_VDD_Override-Pad73)") (class "Default")
      (node (ref "Module1") (pin "73") (pinfunction "SD_VDD_Override_73") (pintype "passive+no_connect"))
    )
    (net (code "89") (name "unconnected-(U5-nc-Pad1)") (class "Default")
      (node (ref "U5") (pin "1") (pinfunction "nc_1") (pintype "passive+no_connect"))
    )
    (net (code "90") (name "unconnected-(U18-nFLG-Pad3)") (class "Default")
      (node (ref "U18") (pin "3") (pinfunction "nFLG_3") (pintype "passive+no_connect"))
    )
  )
)
